# 09_Misc.net
KiCad netlist of a schematic drawn in Altium Designer
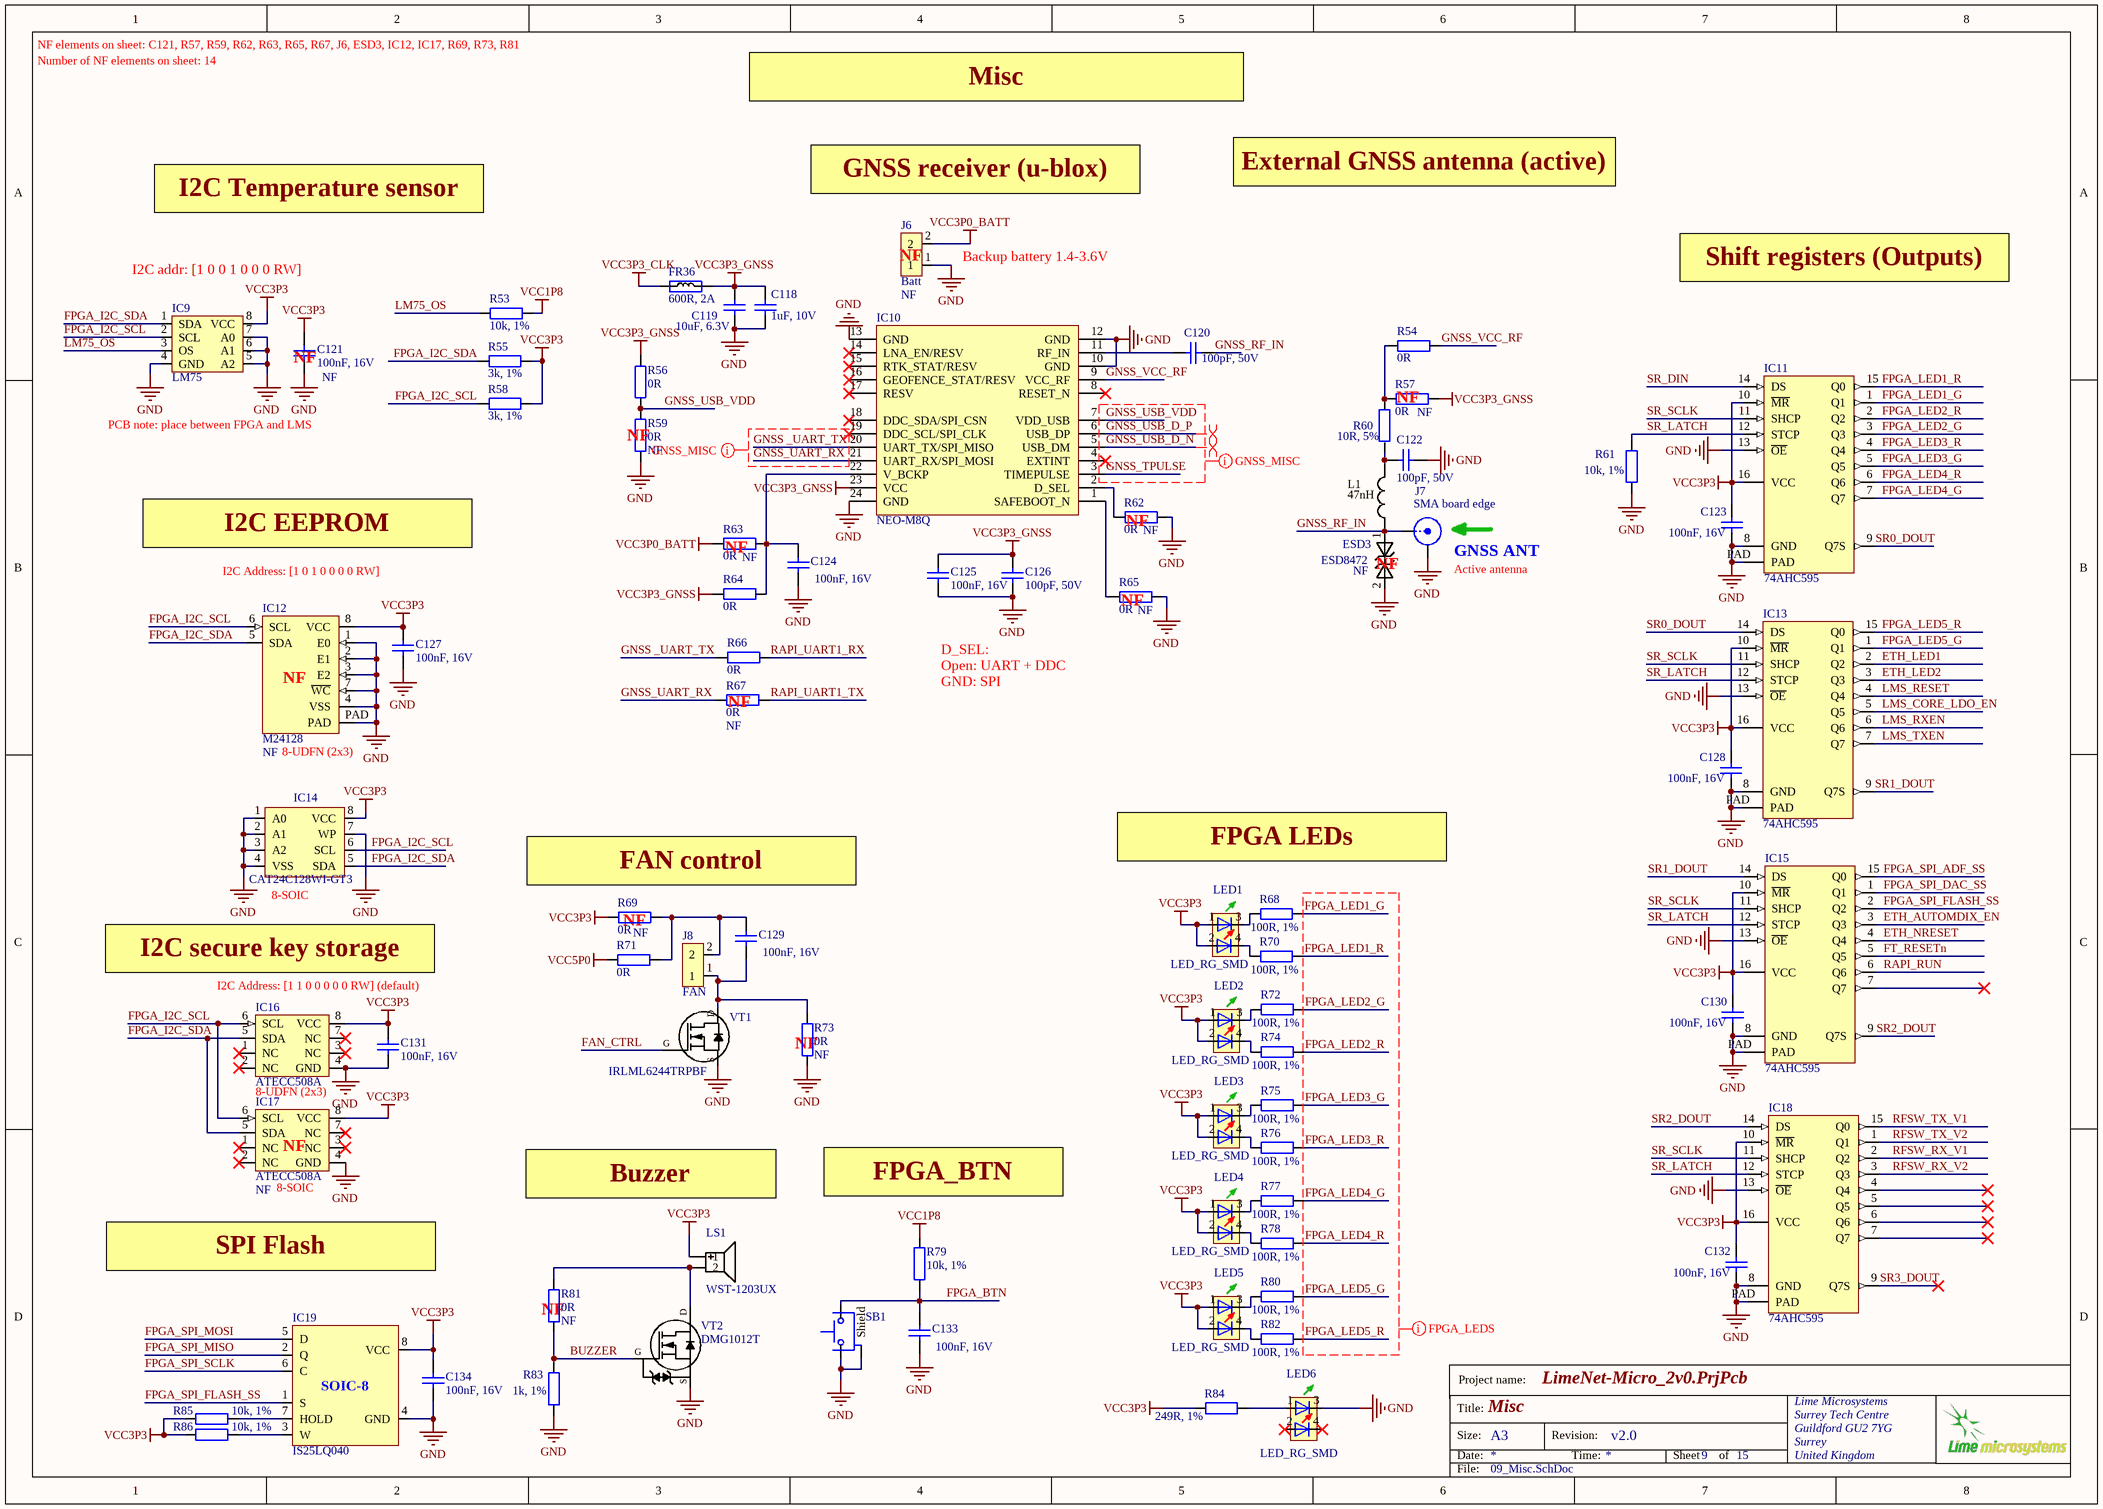
[diagram p0: 09_Misc.SchDoc]

(export (version "E")
  (design (tool "Eeschema 10.0.6"))
  (components
    (comp (ref "C118")
      (value "1uF, 10V")
      (footprint "CAP0402")
      (description "CAP CER 1UF 10V X5R 0402")
      (fields
        (field (name "MANUFACTURER") "Yageo")
        (field (name "MANUFACTURER PART NUMBER") "CC0402MRX5R6BB105")
      )
      (libsource (lib "LimeMicroAltiumLib_schLib") (part "Cap_0402"))
    )
    (comp (ref "C119")
      (value "10uF, 6.3V")
      (footprint "CAP0603")
      (fields (field (name "TOLERANCE") "±20%") (field (name "MANUFACTURER") "Yageo"))
      (libsource (lib "LimeFPGAboard_schLib") (part "Cap_0603"))
    )
    (comp (ref "C120")
      (value "100pF, 50V")
      (footprint "CAP0402")
      (fields (field (name "TOLERANCE") "±5%") (field (name "MANUFACTURER") "Yageo"))
      (libsource (lib "LimeMicroAltiumLib_schLib") (part "Cap_0402"))
    )
    (comp (ref "C121")
      (value "100nF, 16V")
      (footprint "CAP0402")
      (fields
        (field (name "TOLERANCE") "10 %")
        (field (name "MANUFACTURER") "Murata Electronics")
        (field (name "MANUFACTURER PART NUMBER") "GRM155R71C104KA88D")
        (field (name "ASSEMBLY INFO") "NF")
      )
      (libsource (lib "LimeFPGAboard_schLib") (part "Cap_0603"))
    )
    (comp (ref "C122")
      (value "100pF, 50V")
      (footprint "CAP0402")
      (fields (field (name "TOLERANCE") "±5%") (field (name "MANUFACTURER") "Yageo"))
      (libsource (lib "LimeMicroAltiumLib_schLib") (part "Cap_0402"))
    )
    (comp (ref "C123")
      (value "100nF, 16V")
      (footprint "CAP0402")
      (fields
        (field (name "MANUFACTURER") "Murata Electronics")
        (field (name "TOLERANCE") "10 %")
        (field (name "MANUFACTURER PART NUMBER") "GRM155R71C104KA88D")
      )
      (libsource (lib "LimeMicroAltiumLib_schLib") (part "Cap_0402"))
    )
    (comp (ref "C124")
      (value "100nF, 16V")
      (footprint "CAP0402")
      (fields
        (field (name "TOLERANCE") "10 %")
        (field (name "MANUFACTURER") "Murata Electronics")
        (field (name "MANUFACTURER PART NUMBER") "GRM155R71C104KA88D")
      )
      (libsource (lib "LimeFPGAboard_schLib") (part "Cap_0603"))
    )
    (comp (ref "C125")
      (value "100nF, 16V")
      (footprint "CAP0402")
      (fields
        (field (name "MANUFACTURER") "Murata Electronics")
        (field (name "TOLERANCE") "10 %")
        (field (name "MANUFACTURER PART NUMBER") "GRM155R71C104KA88D")
      )
      (libsource (lib "LimeMicroAltiumLib_schLib") (part "Cap_0402"))
    )
    (comp (ref "C126")
      (value "100pF, 50V")
      (footprint "CAP0402")
      (fields (field (name "TOLERANCE") "±5%") (field (name "MANUFACTURER") "Yageo"))
      (libsource (lib "LimeMicroAltiumLib_schLib") (part "Cap_0402"))
    )
    (comp (ref "C127")
      (value "100nF, 16V")
      (footprint "CAP0402")
      (fields
        (field (name "TOLERANCE") "10 %")
        (field (name "MANUFACTURER") "Murata Electronics")
        (field (name "MANUFACTURER PART NUMBER") "GRM155R71C104KA88D")
      )
      (libsource (lib "LimeFPGAboard_schLib") (part "Cap_0603"))
    )
    (comp (ref "C128")
      (value "100nF, 16V")
      (footprint "CAP0402")
      (fields
        (field (name "MANUFACTURER") "Murata Electronics")
        (field (name "TOLERANCE") "10 %")
        (field (name "MANUFACTURER PART NUMBER") "GRM155R71C104KA88D")
      )
      (libsource (lib "LimeMicroAltiumLib_schLib") (part "Cap_0402"))
    )
    (comp (ref "C129")
      (value "100nF, 16V")
      (footprint "CAP0402")
      (fields
        (field (name "TOLERANCE") "10 %")
        (field (name "MANUFACTURER") "Murata Electronics")
        (field (name "MANUFACTURER PART NUMBER") "GRM155R71C104KA88D")
      )
      (libsource (lib "LimeFPGAboard_schLib") (part "Cap_0603"))
    )
    (comp (ref "C130")
      (value "100nF, 16V")
      (footprint "CAP0402")
      (fields
        (field (name "MANUFACTURER") "Murata Electronics")
        (field (name "TOLERANCE") "10 %")
        (field (name "MANUFACTURER PART NUMBER") "GRM155R71C104KA88D")
      )
      (libsource (lib "LimeMicroAltiumLib_schLib") (part "Cap_0402"))
    )
    (comp (ref "C131")
      (value "100nF, 16V")
      (footprint "CAP0402")
      (fields
        (field (name "TOLERANCE") "10 %")
        (field (name "MANUFACTURER") "Murata Electronics")
        (field (name "MANUFACTURER PART NUMBER") "GRM155R71C104KA88D")
      )
      (libsource (lib "LimeFPGAboard_schLib") (part "Cap_0603"))
    )
    (comp (ref "C132")
      (value "100nF, 16V")
      (footprint "CAP0402")
      (fields
        (field (name "MANUFACTURER") "Murata Electronics")
        (field (name "TOLERANCE") "10 %")
        (field (name "MANUFACTURER PART NUMBER") "GRM155R71C104KA88D")
      )
      (libsource (lib "LimeMicroAltiumLib_schLib") (part "Cap_0402"))
    )
    (comp (ref "C133")
      (value "100nF, 16V")
      (footprint "CAP0402")
      (fields
        (field (name "TOLERANCE") "10 %")
        (field (name "MANUFACTURER") "Murata Electronics")
        (field (name "MANUFACTURER PART NUMBER") "GRM155R71C104KA88D")
      )
      (libsource (lib "LimeFPGAboard_schLib") (part "Cap_0603"))
    )
    (comp (ref "C134")
      (value "100nF, 16V")
      (footprint "CAP0402")
      (fields
        (field (name "TOLERANCE") "10 %")
        (field (name "MANUFACTURER") "Murata Electronics")
        (field (name "MANUFACTURER PART NUMBER") "GRM155R71C104KA88D")
      )
      (libsource (lib "LimeFPGAboard_schLib") (part "Cap_0603"))
    )
    (comp (ref "ESD3")
      (value "ESD8472")
      (footprint "ESD8472_X3DFN2")
      (fields
        (field (name "MANUFACTURER") "ON Semiconductor")
        (field (name "MANUFACTURER PART NUMBER") "ESD8472MUT5G")
        (field (name "ASSEMBLY INFO") "NF")
      )
      (libsource (lib "LimeMicroAltiumLib_schLib") (part "ESD8472"))
    )
    (comp (ref "FR36")
      (value "600R, 2A")
      (footprint "RES0805")
      (fields (field (name "MANUFACTURER") "TDK Corporation"))
      (libsource (lib "LimeFPGAboard_schLib") (part "Ferrite"))
    )
    (comp (ref "IC9")
      (value "LM75")
      (footprint "HWSON8_LM75")
      (fields
        (field (name "MANUFACTURER") "NXP Semiconductors")
        (field (name "MANUFACTURER PART NUMBER") "LM75BTP,147")
      )
      (libsource (lib "LimeMicroAltiumLib_schLib") (part "LM75"))
    )
    (comp (ref "IC10")
      (value "NEO-M8Q")
      (footprint "NEO-7M/8M")
      (description "GNSS engine for GPS/QZSS, GLONASS")
      (fields (field (name "MANUFACTURER") "U-blox"))
      (libsource (lib "LimeMicroAltiumLib_schLib") (part "NEO-M8P_M8M"))
    )
    (comp (ref "IC11")
      (value "74AHC595")
      (footprint "74HC595BQ,115")
      (fields (field (name "MANUFACTURER") "Nexperia USA Inc."))
      (libsource (lib "LimeMicroAltiumLib_schLib") (part "74HC595BQ,115"))
    )
    (comp (ref "IC12")
      (value "M24128")
      (footprint "M24128-DFMC6TG")
      (fields (field (name "MANUFACTURER") "STMicroelectronics") (field (name "ASSEMBLY INFO") "NF"))
      (libsource (lib "LimeMicroAltiumLib_schLib") (part "M24128-DFMC6TG"))
    )
    (comp (ref "IC13")
      (value "74AHC595")
      (footprint "74HC595BQ,115")
      (fields (field (name "MANUFACTURER") "Nexperia USA Inc."))
      (libsource (lib "LimeMicroAltiumLib_schLib") (part "74HC595BQ,115"))
    )
    (comp (ref "IC14")
      (value "CAT24C128WI-GT3")
      (footprint "SOIC127P600-8DL_v2")
      (fields (field (name "MANUFACTURER") "ON Semiconductor") (field (name "BASE PART NUMBER") "CAT24C128"))
      (libsource (lib "LimeMicroAltiumLib_schLib") (part "24FC64F"))
    )
    (comp (ref "IC15")
      (value "74AHC595")
      (footprint "74HC595BQ,115")
      (fields (field (name "MANUFACTURER") "Nexperia USA Inc."))
      (libsource (lib "LimeMicroAltiumLib_schLib") (part "74HC595BQ,115"))
    )
    (comp (ref "IC16")
      (value "ATECC508A")
      (footprint "ATECC508A_UDFN8")
      (fields (field (name "MANUFACTURER") "Microchip"))
      (libsource (lib "LimeMicroAltiumLib_schLib_r01") (part "ATECC508A_authentication_IC"))
    )
    (comp (ref "IC17")
      (value "ATECC508A")
      (footprint "SOIC127P600-8DL_v2")
      (fields
        (field (name "ASSEMBLY INFO") "NF")
        (field (name "MANUFACTURER") "Microchip Technology")
        (field (name "BASE PART NUMBER") "ATECC508")
      )
      (libsource (lib "LimeMicroAltiumLib_schLib_r01") (part "ATECC508A_authentication_IC"))
    )
    (comp (ref "IC18")
      (value "74AHC595")
      (footprint "74HC595BQ,115")
      (fields (field (name "MANUFACTURER") "Nexperia USA Inc."))
      (libsource (lib "LimeMicroAltiumLib_schLib") (part "74HC595BQ,115"))
    )
    (comp (ref "IC19")
      (value "IS25LQ040")
      (footprint "M25P40-VMN6TPB_SO8N")
      (fields
        (field (name "MANUFACTURER PART NUMBER") "IS25LQ040B-JNLE")
        (field (name "MANUFACTURER") "ISSI, Integrated Silicon Solution Inc")
      )
      (libsource (lib "LimeFPGAboard_schLib") (part "M25P40"))
    )
    (comp (ref "J6")
      (value "Batt")
      (footprint "HDR_1x2")
      (fields (field (name "ASSEMBLY INFO") "NF") (field (name "MANUFACTURER") "3M"))
      (libsource (lib "LimeFPGAboard_schLib") (part "Jumper"))
    )
    (comp (ref "J7")
      (value "SMA board edge")
      (footprint "SMA_connector_board_edge_SM")
      (description "CONN SMA JACK STR 50OHM EDGE MNT")
      (fields (field (name "MANUFACTURER") "RF Solutions"))
      (libsource (lib "LimeMicroAltiumLib_schLib") (part "RF_IF_connector"))
    )
    (comp (ref "J8")
      (value "FAN")
      (footprint "HDR_1x2")
      (fields (field (name "MANUFACTURER") "3M"))
      (libsource (lib "LimeFPGAboard_schLib") (part "Jumper"))
    )
    (comp (ref "L1")
      (value "47nH")
      (footprint "RES0402")
      (fields
        (field (name "MANUFACTURER") "COILCRAFT")
        (field (name "MANUFACTURER PART NUMBER") "0402HP-47NXJLU")
      )
      (libsource (lib "LimeMicroAltiumLib_schLib") (part "Inductor_0603"))
    )
    (comp (ref "LED1")
      (value "LED_RG_SMD")
      (footprint "LED-2x0603")
      (fields (field (name "MANUFACTURER") "Avago Technologies US Inc."))
      (libsource (lib "LimeMicroAltiumLib_schLib") (part "LED_green_red_SMD"))
    )
    (comp (ref "LED2")
      (value "LED_RG_SMD")
      (footprint "LED-2x0603")
      (fields (field (name "MANUFACTURER") "Avago Technologies US Inc."))
      (libsource (lib "LimeMicroAltiumLib_schLib") (part "LED_green_red_SMD"))
    )
    (comp (ref "LED3")
      (value "LED_RG_SMD")
      (footprint "LED-2x0603")
      (fields (field (name "MANUFACTURER") "Avago Technologies US Inc."))
      (libsource (lib "LimeMicroAltiumLib_schLib") (part "LED_green_red_SMD"))
    )
    (comp (ref "LED4")
      (value "LED_RG_SMD")
      (footprint "LED-2x0603")
      (fields (field (name "MANUFACTURER") "Avago Technologies US Inc."))
      (libsource (lib "LimeMicroAltiumLib_schLib") (part "LED_green_red_SMD"))
    )
    (comp (ref "LED5")
      (value "LED_RG_SMD")
      (footprint "LED-2x0603")
      (fields (field (name "MANUFACTURER") "Avago Technologies US Inc."))
      (libsource (lib "LimeMicroAltiumLib_schLib") (part "LED_green_red_SMD"))
    )
    (comp (ref "LED6")
      (value "LED_RG_SMD")
      (footprint "LED-2x0603")
      (fields (field (name "MANUFACTURER") "Avago Technologies US Inc."))
      (libsource (lib "LimeMicroAltiumLib_schLib") (part "LED_green_red_SMD"))
    )
    (comp (ref "LS1")
      (value "WST-1203UX")
      (footprint "BUZZER_WST-1203UX")
      (fields (field (name "MANUFACTURER") "Soberton Inc."))
      (libsource (lib "LimeMicroAltiumLib_schLib_r01") (part "BUZZER_WST-1203UX"))
    )
    (comp (ref "R53")
      (value "10k, 1%")
      (footprint "RES0402")
      (fields (field (name "MANUFACTURER") "Yageo") (field (name "TOLERANCE") "±1%"))
      (libsource (lib "LimeMicroAltiumLib_schLib") (part "Res_0402"))
    )
    (comp (ref "R54")
      (value "0R")
      (footprint "RES0402")
      (fields (field (name "MANUFACTURER") "Yageo") (field (name "TOLERANCE") "Jumper"))
      (libsource (lib "LimeMicroAltiumLib_schLib") (part "Res_0402"))
    )
    (comp (ref "R55")
      (value "3k, 1%")
      (footprint "RES0402")
      (fields (field (name "TOLERANCE") "±1%") (field (name "MANUFACTURER") "Vishay Dale"))
      (libsource (lib "LimeMicroAltiumLib_schLib") (part "Res_0402"))
    )
    (comp (ref "R56")
      (value "0R")
      (footprint "RES0402")
      (fields (field (name "MANUFACTURER") "Yageo") (field (name "TOLERANCE") "Jumper"))
      (libsource (lib "LimeMicroAltiumLib_schLib") (part "Res_0402"))
    )
    (comp (ref "R57")
      (value "0R")
      (footprint "RES0402")
      (fields
        (field (name "ASSEMBLY INFO") "NF")
        (field (name "MANUFACTURER") "Yageo")
        (field (name "TOLERANCE") "Jumper")
      )
      (libsource (lib "LimeMicroAltiumLib_schLib") (part "Res_0402"))
    )
    (comp (ref "R58")
      (value "3k, 1%")
      (footprint "RES0402")
      (fields (field (name "TOLERANCE") "±1%") (field (name "MANUFACTURER") "Vishay Dale"))
      (libsource (lib "LimeMicroAltiumLib_schLib") (part "Res_0402"))
    )
    (comp (ref "R59")
      (value "0R")
      (footprint "RES0402")
      (fields
        (field (name "ASSEMBLY INFO") "NF")
        (field (name "MANUFACTURER") "Yageo")
        (field (name "TOLERANCE") "Jumper")
      )
      (libsource (lib "LimeMicroAltiumLib_schLib") (part "Res_0402"))
    )
    (comp (ref "R60")
      (value "10R, 5%")
      (footprint "RES0402")
      (fields (field (name "TOLERANCE") "±5%") (field (name "MANUFACTURER") "Yageo"))
      (libsource (lib "LimeMicroAltiumLib_schLib") (part "Res_0402"))
    )
    (comp (ref "R61")
      (value "10k, 1%")
      (footprint "RES0402")
      (fields (field (name "MANUFACTURER") "Yageo") (field (name "TOLERANCE") "±1%"))
      (libsource (lib "LimeMicroAltiumLib_schLib") (part "Res_0402"))
    )
    (comp (ref "R62")
      (value "0R")
      (footprint "RES0402")
      (fields
        (field (name "ASSEMBLY INFO") "NF")
        (field (name "MANUFACTURER") "Yageo")
        (field (name "TOLERANCE") "Jumper")
      )
      (libsource (lib "LimeMicroAltiumLib_schLib") (part "Res_0402"))
    )
    (comp (ref "R63")
      (value "0R")
      (footprint "RES0402")
      (fields
        (field (name "ASSEMBLY INFO") "NF")
        (field (name "MANUFACTURER") "Yageo")
        (field (name "TOLERANCE") "Jumper")
      )
      (libsource (lib "LimeMicroAltiumLib_schLib") (part "Res_0402"))
    )
    (comp (ref "R64")
      (value "0R")
      (footprint "RES0402")
      (fields (field (name "MANUFACTURER") "Yageo") (field (name "TOLERANCE") "Jumper"))
      (libsource (lib "LimeMicroAltiumLib_schLib") (part "Res_0402"))
    )
    (comp (ref "R65")
      (value "0R")
      (footprint "RES0402")
      (fields
        (field (name "ASSEMBLY INFO") "NF")
        (field (name "MANUFACTURER") "Yageo")
        (field (name "TOLERANCE") "Jumper")
      )
      (libsource (lib "LimeMicroAltiumLib_schLib") (part "Res_0402"))
    )
    (comp (ref "R66")
      (value "0R")
      (footprint "RES0402")
      (fields (field (name "MANUFACTURER") "Yageo") (field (name "TOLERANCE") "Jumper"))
      (libsource (lib "LimeMicroAltiumLib_schLib") (part "Res_0402"))
    )
    (comp (ref "R67")
      (value "0R")
      (footprint "RES0402")
      (fields
        (field (name "ASSEMBLY INFO") "NF")
        (field (name "MANUFACTURER") "Yageo")
        (field (name "TOLERANCE") "Jumper")
      )
      (libsource (lib "LimeMicroAltiumLib_schLib") (part "Res_0402"))
    )
    (comp (ref "R68")
      (value "100R, 1%")
      (footprint "RES0402")
      (fields (field (name "TOLERANCE") "±1%") (field (name "MANUFACTURER") "Stackpole Electronics Inc."))
      (libsource (lib "LimeMicroAltiumLib_schLib") (part "Res_0402"))
    )
    (comp (ref "R69")
      (value "0R")
      (footprint "RES0402")
      (fields
        (field (name "ASSEMBLY INFO") "NF")
        (field (name "MANUFACTURER") "Yageo")
        (field (name "TOLERANCE") "Jumper")
      )
      (libsource (lib "LimeMicroAltiumLib_schLib") (part "Res_0402"))
    )
    (comp (ref "R70")
      (value "100R, 1%")
      (footprint "RES0402")
      (fields (field (name "TOLERANCE") "±1%") (field (name "MANUFACTURER") "Stackpole Electronics Inc."))
      (libsource (lib "LimeMicroAltiumLib_schLib") (part "Res_0402"))
    )
    (comp (ref "R71")
      (value "0R")
      (footprint "RES0402")
      (fields (field (name "MANUFACTURER") "Yageo") (field (name "TOLERANCE") "Jumper"))
      (libsource (lib "LimeMicroAltiumLib_schLib") (part "Res_0402"))
    )
    (comp (ref "R72")
      (value "100R, 1%")
      (footprint "RES0402")
      (fields (field (name "TOLERANCE") "±1%") (field (name "MANUFACTURER") "Stackpole Electronics Inc."))
      (libsource (lib "LimeMicroAltiumLib_schLib") (part "Res_0402"))
    )
    (comp (ref "R73")
      (value "0R")
      (footprint "RES0402")
      (fields
        (field (name "ASSEMBLY INFO") "NF")
        (field (name "MANUFACTURER") "Yageo")
        (field (name "TOLERANCE") "Jumper")
      )
      (libsource (lib "LimeMicroAltiumLib_schLib") (part "Res_0402"))
    )
    (comp (ref "R74")
      (value "100R, 1%")
      (footprint "RES0402")
      (fields (field (name "TOLERANCE") "±1%") (field (name "MANUFACTURER") "Stackpole Electronics Inc."))
      (libsource (lib "LimeMicroAltiumLib_schLib") (part "Res_0402"))
    )
    (comp (ref "R75")
      (value "100R, 1%")
      (footprint "RES0402")
      (fields (field (name "TOLERANCE") "±1%") (field (name "MANUFACTURER") "Stackpole Electronics Inc."))
      (libsource (lib "LimeMicroAltiumLib_schLib") (part "Res_0402"))
    )
    (comp (ref "R76")
      (value "100R, 1%")
      (footprint "RES0402")
      (fields (field (name "TOLERANCE") "±1%") (field (name "MANUFACTURER") "Stackpole Electronics Inc."))
      (libsource (lib "LimeMicroAltiumLib_schLib") (part "Res_0402"))
    )
    (comp (ref "R77")
      (value "100R, 1%")
      (footprint "RES0402")
      (fields (field (name "TOLERANCE") "±1%") (field (name "MANUFACTURER") "Stackpole Electronics Inc."))
      (libsource (lib "LimeMicroAltiumLib_schLib") (part "Res_0402"))
    )
    (comp (ref "R78")
      (value "100R, 1%")
      (footprint "RES0402")
      (fields (field (name "TOLERANCE") "±1%") (field (name "MANUFACTURER") "Stackpole Electronics Inc."))
      (libsource (lib "LimeMicroAltiumLib_schLib") (part "Res_0402"))
    )
    (comp (ref "R79")
      (value "10k, 1%")
      (footprint "RES0402")
      (fields (field (name "MANUFACTURER") "Yageo") (field (name "TOLERANCE") "±1%"))
      (libsource (lib "LimeMicroAltiumLib_schLib") (part "Res_0402"))
    )
    (comp (ref "R80")
      (value "100R, 1%")
      (footprint "RES0402")
      (fields (field (name "TOLERANCE") "±1%") (field (name "MANUFACTURER") "Stackpole Electronics Inc."))
      (libsource (lib "LimeMicroAltiumLib_schLib") (part "Res_0402"))
    )
    (comp (ref "R81")
      (value "0R")
      (footprint "RES0402")
      (fields
        (field (name "ASSEMBLY INFO") "NF")
        (field (name "MANUFACTURER") "Yageo")
        (field (name "TOLERANCE") "Jumper")
      )
      (libsource (lib "LimeMicroAltiumLib_schLib") (part "Res_0402"))
    )
    (comp (ref "R82")
      (value "100R, 1%")
      (footprint "RES0402")
      (fields (field (name "TOLERANCE") "±1%") (field (name "MANUFACTURER") "Stackpole Electronics Inc."))
      (libsource (lib "LimeMicroAltiumLib_schLib") (part "Res_0402"))
    )
    (comp (ref "R83")
      (value "1k, 1%")
      (footprint "RES0402")
      (fields (field (name "MANUFACTURER") "Stackpole Electronics Inc") (field (name "TOLERANCE") "±1%"))
      (libsource (lib "LimeMicroAltiumLib_schLib") (part "Res_0402"))
    )
    (comp (ref "R84")
      (value "249R, 1%")
      (footprint "RES0402")
      (fields (field (name "MANUFACTURER") "Stackpole Electronics Inc") (field (name "TOLERANCE") "±1%"))
      (libsource (lib "LimeMicroAltiumLib_schLib") (part "Res_0402"))
    )
    (comp (ref "R85")
      (value "10k, 1%")
      (footprint "RES0402")
      (fields (field (name "MANUFACTURER") "Yageo") (field (name "TOLERANCE") "±1%"))
      (libsource (lib "LimeMicroAltiumLib_schLib") (part "Res_0402"))
    )
    (comp (ref "R86")
      (value "10k, 1%")
      (footprint "RES0402")
      (fields (field (name "MANUFACTURER") "Yageo") (field (name "TOLERANCE") "±1%"))
      (libsource (lib "LimeMicroAltiumLib_schLib") (part "Res_0402"))
    )
    (comp (ref "SB1")
      (value "Switch tactile right edge")
      (footprint "SW_TACTILE_RIGHT_EDGE")
      (fields (field (name "MANUFACTURER") "TE Connectivity ALCOSWITCH Switches"))
      (libsource (lib "LimeMicroAltiumLib_schLib_r01") (part "Button_right_edge"))
    )
    (comp (ref "VT1")
      (value "IRLML6244TRPBF")
      (footprint "SOT23-3")
      (description "NDS331N")
      (fields (field (name "MANUFACTURER") "Infineon Technologies"))
      (libsource (lib "LimeFPGAboard_schLib") (part "NDS331N"))
    )
    (comp (ref "VT2")
      (value "DMG1012T")
      (footprint "SOT523")
      (fields
        (field (name "MANUFACTURER") "Diodes Incorporated")
        (field (name "MANUFACTURER PART NUMBER") "DMG1012TQ-7")
      )
      (libsource (lib "LimeMicroAltiumLib_schLib_r01") (part "DMG1012T"))
    )
  )
  (nets
    (net (code "1") (name "/BUZZER") (class "Default")
      (node (ref "R81") (pin "1") (pinfunction "1_1") (pintype "passive"))
      (node (ref "R83") (pin "1") (pinfunction "1_1") (pintype "passive"))
      (node (ref "VT2") (pin "G") (pinfunction "G_G") (pintype "passive"))
    )
    (net (code "2") (name "/ETH_AUTOMDIX_EN") (class "Default")
      (node (ref "IC15") (pin "3") (pinfunction "Q3_3") (pintype "output"))
    )
    (net (code "3") (name "/ETH_LED1") (class "Default")
      (node (ref "IC13") (pin "2") (pinfunction "Q2_2") (pintype "output"))
    )
    (net (code "4") (name "/ETH_LED2") (class "Default")
      (node (ref "IC13") (pin "3") (pinfunction "Q3_3") (pintype "output"))
    )
    (net (code "5") (name "/ETH_NRESET") (class "Default")
      (node (ref "IC15") (pin "4") (pinfunction "Q4_4") (pintype "output"))
    )
    (net (code "6") (name "/FAN_CTRL") (class "Default")
      (node (ref "VT1") (pin "G") (pinfunction "G_G") (pintype "passive"))
    )
    (net (code "7") (name "/FPGA_BTN") (class "Default")
      (node (ref "C133") (pin "1") (pinfunction "1_1") (pintype "passive"))
      (node (ref "R79") (pin "2") (pinfunction "2_2") (pintype "passive"))
      (node (ref "SB1") (pin "1") (pinfunction "1_1") (pintype "passive"))
    )
    (net (code "8") (name "/FPGA_I2C_SCL") (class "Default")
      (node (ref "IC12") (pin "6") (pinfunction "SCL_6") (pintype "input"))
      (node (ref "IC14") (pin "6") (pinfunction "SCL_6") (pintype "passive"))
      (node (ref "IC16") (pin "6") (pinfunction "SCL_6") (pintype "input"))
      (node (ref "IC17") (pin "6") (pinfunction "SCL_6") (pintype "input"))
      (node (ref "IC9") (pin "2") (pinfunction "SCL_2") (pintype "passive"))
      (node (ref "R58") (pin "2") (pinfunction "2_2") (pintype "passive"))
    )
    (net (code "9") (name "/FPGA_I2C_SDA") (class "Default")
      (node (ref "IC12") (pin "5") (pinfunction "SDA_5") (pintype "bidirectional"))
      (node (ref "IC14") (pin "5") (pinfunction "SDA_5") (pintype "passive"))
      (node (ref "IC16") (pin "5") (pinfunction "SDA_5") (pintype "bidirectional"))
      (node (ref "IC17") (pin "5") (pinfunction "SDA_5") (pintype "bidirectional"))
      (node (ref "IC9") (pin "1") (pinfunction "SDA_1") (pintype "passive"))
      (node (ref "R55") (pin "2") (pinfunction "2_2") (pintype "passive"))
    )
    (net (code "10") (name "/FPGA_LED1_G") (class "Default")
      (node (ref "IC11") (pin "1") (pinfunction "Q1_1") (pintype "output"))
      (node (ref "R68") (pin "2") (pinfunction "2_2") (pintype "passive"))
    )
    (net (code "11") (name "/FPGA_LED1_R") (class "Default")
      (node (ref "IC11") (pin "15") (pinfunction "Q0_15") (pintype "output"))
      (node (ref "R70") (pin "2") (pinfunction "2_2") (pintype "passive"))
    )
    (net (code "12") (name "/FPGA_LED2_G") (class "Default")
      (node (ref "IC11") (pin "3") (pinfunction "Q3_3") (pintype "output"))
      (node (ref "R72") (pin "2") (pinfunction "2_2") (pintype "passive"))
    )
    (net (code "13") (name "/FPGA_LED2_R") (class "Default")
      (node (ref "IC11") (pin "2") (pinfunction "Q2_2") (pintype "output"))
      (node (ref "R74") (pin "2") (pinfunction "2_2") (pintype "passive"))
    )
    (net (code "14") (name "/FPGA_LED3_G") (class "Default")
      (node (ref "IC11") (pin "5") (pinfunction "Q5_5") (pintype "output"))
      (node (ref "R75") (pin "2") (pinfunction "2_2") (pintype "passive"))
    )
    (net (code "15") (name "/FPGA_LED3_R") (class "Default")
      (node (ref "IC11") (pin "4") (pinfunction "Q4_4") (pintype "output"))
      (node (ref "R76") (pin "2") (pinfunction "2_2") (pintype "passive"))
    )
    (net (code "16") (name "/FPGA_LED4_G") (class "Default")
      (node (ref "IC11") (pin "7") (pinfunction "Q7_7") (pintype "output"))
      (node (ref "R77") (pin "2") (pinfunction "2_2") (pintype "passive"))
    )
    (net (code "17") (name "/FPGA_LED4_R") (class "Default")
      (node (ref "IC11") (pin "6") (pinfunction "Q6_6") (pintype "output"))
      (node (ref "R78") (pin "2") (pinfunction "2_2") (pintype "passive"))
    )
    (net (code "18") (name "/FPGA_LED5_G") (class "Default")
      (node (ref "IC13") (pin "1") (pinfunction "Q1_1") (pintype "output"))
      (node (ref "R80") (pin "2") (pinfunction "2_2") (pintype "passive"))
    )
    (net (code "19") (name "/FPGA_LED5_R") (class "Default")
      (node (ref "IC13") (pin "15") (pinfunction "Q0_15") (pintype "output"))
      (node (ref "R82") (pin "2") (pinfunction "2_2") (pintype "passive"))
    )
    (net (code "20") (name "/FPGA_SPI_ADF_SS") (class "Default")
      (node (ref "IC15") (pin "15") (pinfunction "Q0_15") (pintype "output"))
    )
    (net (code "21") (name "/FPGA_SPI_DAC_SS") (class "Default")
      (node (ref "IC15") (pin "1") (pinfunction "Q1_1") (pintype "output"))
    )
    (net (code "22") (name "/FPGA_SPI_FLASH_SS") (class "Default")
      (node (ref "IC15") (pin "2") (pinfunction "Q2_2") (pintype "output"))
      (node (ref "IC19") (pin "1") (pinfunction "S_1") (pintype "passive"))
    )
    (net (code "23") (name "/FPGA_SPI_MISO") (class "Default")
      (node (ref "IC19") (pin "2") (pinfunction "Q_2") (pintype "passive"))
    )
    (net (code "24") (name "/FPGA_SPI_MOSI") (class "Default")
      (node (ref "IC19") (pin "5") (pinfunction "D_5") (pintype "passive"))
    )
    (net (code "25") (name "/FPGA_SPI_SCLK") (class "Default")
      (node (ref "IC19") (pin "6") (pinfunction "C_6") (pintype "passive"))
    )
    (net (code "26") (name "/FT_RESETn") (class "Default")
      (node (ref "IC15") (pin "5") (pinfunction "Q5_5") (pintype "output"))
    )
    (net (code "27") (name "/GNSS _UART_TX") (class "Default")
      (node (ref "IC10") (pin "20") (pinfunction "UART_TX/SPI_MISO_20") (pintype "passive"))
      (node (ref "R66") (pin "2") (pinfunction "2_2") (pintype "passive"))
    )
    (net (code "28") (name "/GNSS_RF_IN") (class "Default")
      (node (ref "C120") (pin "1") (pinfunction "1_1") (pintype "passive"))
      (node (ref "ESD3") (pin "1") (pinfunction "1_1") (pintype "passive"))
      (node (ref "J7") (pin "1") (pinfunction "X_1") (pintype "passive"))
      (node (ref "L1") (pin "1") (pinfunction "1_1") (pintype "passive"))
    )
    (net (code "29") (name "/GNSS_TPULSE") (class "Default")
      (node (ref "IC10") (pin "3") (pinfunction "TIMEPULSE_3") (pintype "passive"))
    )
    (net (code "30") (name "/GNSS_UART_RX") (class "Default")
      (node (ref "IC10") (pin "21") (pinfunction "UART_RX/SPI_MOSI_21") (pintype "passive"))
      (node (ref "R67") (pin "1") (pinfunction "1_1") (pintype "passive"))
    )
    (net (code "31") (name "/GNSS_USB_D_N") (class "Default")
      (node (ref "IC10") (pin "5") (pinfunction "USB_DM_5") (pintype "passive"))
    )
    (net (code "32") (name "/GNSS_USB_D_P") (class "Default")
      (node (ref "IC10") (pin "6") (pinfunction "USB_DP_6") (pintype "passive"))
    )
    (net (code "33") (name "/GNSS_USB_VDD") (class "Default")
      (node (ref "IC10") (pin "7") (pinfunction "VDD_USB_7") (pintype "passive"))
      (node (ref "R56") (pin "1") (pinfunction "1_1") (pintype "passive"))
      (node (ref "R59") (pin "1") (pinfunction "1_1") (pintype "passive"))
    )
    (net (code "34") (name "/GNSS_VCC_RF") (class "Default")
      (node (ref "IC10") (pin "9") (pinfunction "VCC_RF_9") (pintype "passive"))
      (node (ref "R54") (pin "2") (pinfunction "2_2") (pintype "passive"))
    )
    (net (code "35") (name "/LM75_OS") (class "Default")
      (node (ref "IC9") (pin "3") (pinfunction "OS_3") (pintype "passive"))
      (node (ref "R53") (pin "1") (pinfunction "1_1") (pintype "passive"))
    )
    (net (code "36") (name "/LMS_CORE_LDO_EN") (class "Default")
      (node (ref "IC13") (pin "5") (pinfunction "Q5_5") (pintype "output"))
    )
    (net (code "37") (name "/LMS_RESET") (class "Default")
      (node (ref "IC13") (pin "4") (pinfunction "Q4_4") (pintype "output"))
    )
    (net (code "38") (name "/LMS_RXEN") (class "Default")
      (node (ref "IC13") (pin "6") (pinfunction "Q6_6") (pintype "output"))
    )
    (net (code "39") (name "/LMS_TXEN") (class "Default")
      (node (ref "IC13") (pin "7") (pinfunction "Q7_7") (pintype "output"))
    )
    (net (code "40") (name "/RAPI_RUN") (class "Default")
      (node (ref "IC15") (pin "6") (pinfunction "Q6_6") (pintype "output"))
    )
    (net (code "41") (name "/RAPI_UART1_RX") (class "Default")
      (node (ref "R66") (pin "1") (pinfunction "1_1") (pintype "passive"))
    )
    (net (code "42") (name "/RAPI_UART1_TX") (class "Default")
      (node (ref "R67") (pin "2") (pinfunction "2_2") (pintype "passive"))
    )
    (net (code "43") (name "/RFSW_RX_V1") (class "Default")
      (node (ref "IC18") (pin "2") (pinfunction "Q2_2") (pintype "output"))
    )
    (net (code "44") (name "/RFSW_RX_V2") (class "Default")
      (node (ref "IC18") (pin "3") (pinfunction "Q3_3") (pintype "output"))
    )
    (net (code "45") (name "/RFSW_TX_V1") (class "Default")
      (node (ref "IC18") (pin "15") (pinfunction "Q0_15") (pintype "output"))
    )
    (net (code "46") (name "/RFSW_TX_V2") (class "Default")
      (node (ref "IC18") (pin "1") (pinfunction "Q1_1") (pintype "output"))
    )
    (net (code "47") (name "/SR0_DOUT") (class "Default")
      (node (ref "IC11") (pin "9") (pinfunction "Q7S_9") (pintype "output"))
      (node (ref "IC13") (pin "14") (pinfunction "DS_14") (pintype "input"))
    )
    (net (code "48") (name "/SR1_DOUT") (class "Default")
      (node (ref "IC13") (pin "9") (pinfunction "Q7S_9") (pintype "output"))
      (node (ref "IC15") (pin "14") (pinfunction "DS_14") (pintype "input"))
    )
    (net (code "49") (name "/SR2_DOUT") (class "Default")
      (node (ref "IC15") (pin "9") (pinfunction "Q7S_9") (pintype "output"))
      (node (ref "IC18") (pin "14") (pinfunction "DS_14") (pintype "input"))
    )
    (net (code "50") (name "/SR3_DOUT") (class "Default")
      (node (ref "IC18") (pin "9") (pinfunction "Q7S_9") (pintype "output+no_connect"))
    )
    (net (code "51") (name "/SR_DIN") (class "Default")
      (node (ref "IC11") (pin "14") (pinfunction "DS_14") (pintype "input"))
    )
    (net (code "52") (name "/SR_LATCH") (class "Default")
      (node (ref "IC11") (pin "12") (pinfunction "STCP_12") (pintype "input"))
      (node (ref "IC13") (pin "12") (pinfunction "STCP_12") (pintype "input"))
      (node (ref "IC15") (pin "12") (pinfunction "STCP_12") (pintype "input"))
      (node (ref "IC18") (pin "12") (pinfunction "STCP_12") (pintype "input"))
      (node (ref "R61") (pin "1") (pinfunction "1_1") (pintype "passive"))
    )
    (net (code "53") (name "/SR_SCLK") (class "Default")
      (node (ref "IC11") (pin "11") (pinfunction "SHCP_11") (pintype "input"))
      (node (ref "IC13") (pin "11") (pinfunction "SHCP_11") (pintype "input"))
      (node (ref "IC15") (pin "11") (pinfunction "SHCP_11") (pintype "input"))
      (node (ref "IC18") (pin "11") (pinfunction "SHCP_11") (pintype "input"))
    )
    (net (code "54") (name "GND") (class "Default")
      (node (ref "C118") (pin "1") (pinfunction "1_1") (pintype "passive"))
      (node (ref "C119") (pin "1") (pinfunction "1_1") (pintype "passive"))
      (node (ref "C121") (pin "2") (pinfunction "2_2") (pintype "passive"))
      (node (ref "C122") (pin "2") (pinfunction "2_2") (pintype "passive"))
      (node (ref "C123") (pin "1") (pinfunction "1_1") (pintype "passive"))
      (node (ref "C124") (pin "2") (pinfunction "2_2") (pintype "passive"))
      (node (ref "C125") (pin "1") (pinfunction "1_1") (pintype "passive"))
      (node (ref "C126") (pin "2") (pinfunction "2_2") (pintype "passive"))
      (node (ref "C127") (pin "2") (pinfunction "2_2") (pintype "passive"))
      (node (ref "C128") (pin "1") (pinfunction "1_1") (pintype "passive"))
      (node (ref "C130") (pin "1") (pinfunction "1_1") (pintype "passive"))
      (node (ref "C131") (pin "2") (pinfunction "2_2") (pintype "passive"))
      (node (ref "C132") (pin "1") (pinfunction "1_1") (pintype "passive"))
      (node (ref "C133") (pin "2") (pinfunction "2_2") (pintype "passive"))
      (node (ref "C134") (pin "2") (pinfunction "2_2") (pintype "passive"))
      (node (ref "ESD3") (pin "2") (pinfunction "2_2") (pintype "passive"))
      (node (ref "IC10") (pin "10") (pinfunction "GND_10") (pintype "passive"))
      (node (ref "IC10") (pin "12") (pinfunction "GND_12") (pintype "passive"))
      (node (ref "IC10") (pin "13") (pinfunction "GND_13") (pintype "passive"))
      (node (ref "IC10") (pin "24") (pinfunction "GND_24") (pintype "passive"))
      (node (ref "IC11") (pin "13") (pinfunction "~{OE}_13") (pintype "input"))
      (node (ref "IC11") (pin "8") (pinfunction "GND_8") (pintype "passive"))
      (node (ref "IC11") (pin "PAD") (pinfunction "PAD_PAD") (pintype "passive"))
      (node (ref "IC12") (pin "1") (pinfunction "E0_1") (pintype "input"))
      (node (ref "IC12") (pin "2") (pinfunction "E1_2") (pintype "input"))
      (node (ref "IC12") (pin "3") (pinfunction "E2_3") (pintype "input"))
      (node (ref "IC12") (pin "4") (pinfunction "VSS_4") (pintype "power_in"))
      (node (ref "IC12") (pin "7") (pinfunction "~{WC}_7") (pintype "input"))
      (node (ref "IC12") (pin "PAD") (pinfunction "PAD_PAD") (pintype "power_in"))
      (node (ref "IC13") (pin "13") (pinfunction "~{OE}_13") (pintype "input"))
      (node (ref "IC13") (pin "8") (pinfunction "GND_8") (pintype "passive"))
      (node (ref "IC13") (pin "PAD") (pinfunction "PAD_PAD") (pintype "passive"))
      (node (ref "IC14") (pin "1") (pinfunction "A0_1") (pintype "passive"))
      (node (ref "IC14") (pin "2") (pinfunction "A1_2") (pintype "passive"))
      (node (ref "IC14") (pin "3") (pinfunction "A2_3") (pintype "passive"))
      (node (ref "IC14") (pin "4") (pinfunction "VSS_4") (pintype "passive"))
      (node (ref "IC14") (pin "7") (pinfunction "WP_7") (pintype "passive"))
      (node (ref "IC15") (pin "13") (pinfunction "~{OE}_13") (pintype "input"))
      (node (ref "IC15") (pin "8") (pinfunction "GND_8") (pintype "passive"))
      (node (ref "IC15") (pin "PAD") (pinfunction "PAD_PAD") (pintype "passive"))
      (node (ref "IC16") (pin "4") (pinfunction "GND_4") (pintype "passive"))
      (node (ref "IC17") (pin "4") (pinfunction "GND_4") (pintype "passive"))
      (node (ref "IC18") (pin "13") (pinfunction "~{OE}_13") (pintype "input"))
      (node (ref "IC18") (pin "8") (pinfunction "GND_8") (pintype "passive"))
      (node (ref "IC18") (pin "PAD") (pinfunction "PAD_PAD") (pintype "passive"))
      (node (ref "IC19") (pin "4") (pinfunction "GND_4") (pintype "passive"))
      (node (ref "IC9") (pin "4") (pinfunction "GND_4") (pintype "passive"))
      (node (ref "IC9") (pin "5") (pinfunction "A2_5") (pintype "passive"))
      (node (ref "IC9") (pin "6") (pinfunction "A1_6") (pintype "passive"))
      (node (ref "IC9") (pin "7") (pinfunction "A0_7") (pintype "passive"))
      (node (ref "J6") (pin "1") (pinfunction "1_1") (pintype "passive"))
      (node (ref "J7") (pin "2") (pinfunction "Y_2") (pintype "passive"))
      (node (ref "LED6") (pin "3") (pinfunction "3_3") (pintype "power_in"))
      (node (ref "R59") (pin "2") (pinfunction "2_2") (pintype "passive"))
      (node (ref "R61") (pin "2") (pinfunction "2_2") (pintype "passive"))
      (node (ref "R62") (pin "1") (pinfunction "1_1") (pintype "passive"))
      (node (ref "R65") (pin "1") (pinfunction "1_1") (pintype "passive"))
      (node (ref "R73") (pin "1") (pinfunction "1_1") (pintype "passive"))
      (node (ref "R83") (pin "2") (pinfunction "2_2") (pintype "passive"))
      (node (ref "SB1") (pin "2") (pinfunction "2_2") (pintype "passive"))
      (node (ref "SB1") (pin "Shield") (pinfunction "Shield_Shield") (pintype "passive"))
      (node (ref "VT1") (pin "S") (pinfunction "S_S") (pintype "passive"))
      (node (ref "VT2") (pin "S") (pinfunction "S_S") (pintype "passive"))
    )
    (net (code "55") (name "Net-(C122-Pad1)") (class "Default")
      (node (ref "C122") (pin "1") (pinfunction "1_1") (pintype "passive"))
      (node (ref "L1") (pin "2") (pinfunction "2_2") (pintype "passive"))
      (node (ref "R60") (pin "2") (pinfunction "2_2") (pintype "passive"))
    )
    (net (code "56") (name "Net-(C129-Pad1)") (class "Default")
      (node (ref "C129") (pin "1") (pinfunction "1_1") (pintype "passive"))
      (node (ref "J8") (pin "2") (pinfunction "2_2") (pintype "passive"))
      (node (ref "R69") (pin "2") (pinfunction "2_2") (pintype "passive"))
      (node (ref "R71") (pin "2") (pinfunction "2_2") (pintype "passive"))
    )
    (net (code "57") (name "Net-(C129-Pad2)") (class "Default")
      (node (ref "C129") (pin "2") (pinfunction "2_2") (pintype "passive"))
      (node (ref "J8") (pin "1") (pinfunction "1_1") (pintype "passive"))
      (node (ref "R73") (pin "2") (pinfunction "2_2") (pintype "passive"))
      (node (ref "VT1") (pin "D") (pinfunction "D_D") (pintype "passive"))
    )
    (net (code "58") (name "Net-(IC10-D_SEL)") (class "Default")
      (node (ref "IC10") (pin "2") (pinfunction "D_SEL_2") (pintype "passive"))
      (node (ref "R62") (pin "2") (pinfunction "2_2") (pintype "passive"))
    )
    (net (code "59") (name "Net-(IC10-RF_IN)") (class "Default")
      (node (ref "C120") (pin "2") (pinfunction "2_2") (pintype "passive"))
      (node (ref "IC10") (pin "11") (pinfunction "RF_IN_11") (pintype "passive"))
    )
    (net (code "60") (name "Net-(IC10-SAFEBOOT_N)") (class "Default")
      (node (ref "IC10") (pin "1") (pinfunction "SAFEBOOT_N_1") (pintype "passive"))
      (node (ref "R65") (pin "2") (pinfunction "2_2") (pintype "passive"))
    )
    (net (code "61") (name "Net-(IC10-V_BCKP)") (class "Default")
      (node (ref "C124") (pin "1") (pinfunction "1_1") (pintype "passive"))
      (node (ref "IC10") (pin "22") (pinfunction "V_BCKP_22") (pintype "passive"))
      (node (ref "R63") (pin "1") (pinfunction "1_1") (pintype "passive"))
      (node (ref "R64") (pin "1") (pinfunction "1_1") (pintype "passive"))
    )
    (net (code "62") (name "Net-(IC19-HOLD)") (class "Default")
      (node (ref "IC19") (pin "7") (pinfunction "HOLD_7") (pintype "passive"))
      (node (ref "R85") (pin "2") (pinfunction "2_2") (pintype "passive"))
    )
    (net (code "63") (name "Net-(IC19-W)") (class "Default")
      (node (ref "IC19") (pin "3") (pinfunction "W_3") (pintype "passive"))
      (node (ref "R86") (pin "2") (pinfunction "2_2") (pintype "passive"))
    )
    (net (code "64") (name "Net-(LED1-Pad3)") (class "Default")
      (node (ref "LED1") (pin "3") (pinfunction "3_3") (pintype "power_in"))
      (node (ref "R68") (pin "1") (pinfunction "1_1") (pintype "passive"))
    )
    (net (code "65") (name "Net-(LED1-Pad4)") (class "Default")
      (node (ref "LED1") (pin "4") (pinfunction "4_4") (pintype "power_in"))
      (node (ref "R70") (pin "1") (pinfunction "1_1") (pintype "passive"))
    )
    (net (code "66") (name "Net-(LED2-Pad3)") (class "Default")
      (node (ref "LED2") (pin "3") (pinfunction "3_3") (pintype "power_in"))
      (node (ref "R72") (pin "1") (pinfunction "1_1") (pintype "passive"))
    )
    (net (code "67") (name "Net-(LED2-Pad4)") (class "Default")
      (node (ref "LED2") (pin "4") (pinfunction "4_4") (pintype "power_in"))
      (node (ref "R74") (pin "1") (pinfunction "1_1") (pintype "passive"))
    )
    (net (code "68") (name "Net-(LED3-Pad3)") (class "Default")
      (node (ref "LED3") (pin "3") (pinfunction "3_3") (pintype "power_in"))
      (node (ref "R75") (pin "1") (pinfunction "1_1") (pintype "passive"))
    )
    (net (code "69") (name "Net-(LED3-Pad4)") (class "Default")
      (node (ref "LED3") (pin "4") (pinfunction "4_4") (pintype "power_in"))
      (node (ref "R76") (pin "1") (pinfunction "1_1") (pintype "passive"))
    )
    (net (code "70") (name "Net-(LED4-Pad3)") (class "Default")
      (node (ref "LED4") (pin "3") (pinfunction "3_3") (pintype "power_in"))
      (node (ref "R77") (pin "1") (pinfunction "1_1") (pintype "passive"))
    )
    (net (code "71") (name "Net-(LED4-Pad4)") (class "Default")
      (node (ref "LED4") (pin "4") (pinfunction "4_4") (pintype "power_in"))
      (node (ref "R78") (pin "1") (pinfunction "1_1") (pintype "passive"))
    )
    (net (code "72") (name "Net-(LED5-Pad3)") (class "Default")
      (node (ref "LED5") (pin "3") (pinfunction "3_3") (pintype "power_in"))
      (node (ref "R80") (pin "1") (pinfunction "1_1") (pintype "passive"))
    )
    (net (code "73") (name "Net-(LED5-Pad4)") (class "Default")
      (node (ref "LED5") (pin "4") (pinfunction "4_4") (pintype "power_in"))
      (node (ref "R82") (pin "1") (pinfunction "1_1") (pintype "passive"))
    )
    (net (code "74") (name "Net-(LED6-Pad1)") (class "Default")
      (node (ref "LED6") (pin "1") (pinfunction "1_1") (pintype "power_in"))
      (node (ref "R84") (pin "2") (pinfunction "2_2") (pintype "passive"))
    )
    (net (code "75") (name "Net-(LS1-Pad2)") (class "Default")
      (node (ref "LS1") (pin "2") (pinfunction "2_2") (pintype "passive"))
      (node (ref "R81") (pin "2") (pinfunction "2_2") (pintype "passive"))
      (node (ref "VT2") (pin "D") (pinfunction "D_D") (pintype "passive"))
    )
    (net (code "76") (name "Net-(R54-Pad1)") (class "Default")
      (node (ref "R54") (pin "1") (pinfunction "1_1") (pintype "passive"))
      (node (ref "R57") (pin "2") (pinfunction "2_2") (pintype "passive"))
      (node (ref "R60") (pin "1") (pinfunction "1_1") (pintype "passive"))
    )
    (net (code "77") (name "VCC1P8") (class "Default")
      (node (ref "R53") (pin "2") (pinfunction "2_2") (pintype "passive"))
      (node (ref "R79") (pin "1") (pinfunction "1_1") (pintype "passive"))
    )
    (net (code "78") (name "VCC3P0_BATT") (class "Default")
      (node (ref "J6") (pin "2") (pinfunction "2_2") (pintype "passive"))
      (node (ref "R63") (pin "2") (pinfunction "2_2") (pintype "passive"))
    )
    (net (code "79") (name "VCC3P3") (class "Default")
      (node (ref "C121") (pin "1") (pinfunction "1_1") (pintype "passive"))
      (node (ref "C123") (pin "2") (pinfunction "2_2") (pintype "passive"))
      (node (ref "C127") (pin "1") (pinfunction "1_1") (pintype "passive"))
      (node (ref "C128") (pin "2") (pinfunction "2_2") (pintype "passive"))
      (node (ref "C130") (pin "2") (pinfunction "2_2") (pintype "passive"))
      (node (ref "C131") (pin "1") (pinfunction "1_1") (pintype "passive"))
      (node (ref "C132") (pin "2") (pinfunction "2_2") (pintype "passive"))
      (node (ref "C134") (pin "1") (pinfunction "1_1") (pintype "passive"))
      (node (ref "IC11") (pin "10") (pinfunction "~{MR}_10") (pintype "input"))
      (node (ref "IC11") (pin "16") (pinfunction "VCC_16") (pintype "power_in"))
      (node (ref "IC12") (pin "8") (pinfunction "VCC_8") (pintype "power_in"))
      (node (ref "IC13") (pin "10") (pinfunction "~{MR}_10") (pintype "input"))
      (node (ref "IC13") (pin "16") (pinfunction "VCC_16") (pintype "power_in"))
      (node (ref "IC14") (pin "8") (pinfunction "VCC_8") (pintype "passive"))
      (node (ref "IC15") (pin "10") (pinfunction "~{MR}_10") (pintype "input"))
      (node (ref "IC15") (pin "16") (pinfunction "VCC_16") (pintype "power_in"))
      (node (ref "IC16") (pin "8") (pinfunction "VCC_8") (pintype "power_in"))
      (node (ref "IC17") (pin "8") (pinfunction "VCC_8") (pintype "power_in"))
      (node (ref "IC18") (pin "10") (pinfunction "~{MR}_10") (pintype "input"))
      (node (ref "IC18") (pin "16") (pinfunction "VCC_16") (pintype "power_in"))
      (node (ref "IC19") (pin "8") (pinfunction "VCC_8") (pintype "passive"))
      (node (ref "IC9") (pin "8") (pinfunction "VCC_8") (pintype "passive"))
      (node (ref "LED1") (pin "1") (pinfunction "1_1") (pintype "power_in"))
      (node (ref "LED1") (pin "2") (pinfunction "2_2") (pintype "power_in"))
      (node (ref "LED2") (pin "1") (pinfunction "1_1") (pintype "power_in"))
      (node (ref "LED2") (pin "2") (pinfunction "2_2") (pintype "power_in"))
      (node (ref "LED3") (pin "1") (pinfunction "1_1") (pintype "power_in"))
      (node (ref "LED3") (pin "2") (pinfunction "2_2") (pintype "power_in"))
      (node (ref "LED4") (pin "1") (pinfunction "1_1") (pintype "power_in"))
      (node (ref "LED4") (pin "2") (pinfunction "2_2") (pintype "power_in"))
      (node (ref "LED5") (pin "1") (pinfunction "1_1") (pintype "power_in"))
      (node (ref "LED5") (pin "2") (pinfunction "2_2") (pintype "power_in"))
      (node (ref "LS1") (pin "1") (pinfunction "1_1") (pintype "passive"))
      (node (ref "R55") (pin "1") (pinfunction "1_1") (pintype "passive"))
      (node (ref "R58") (pin "1") (pinfunction "1_1") (pintype "passive"))
      (node (ref "R69") (pin "1") (pinfunction "1_1") (pintype "passive"))
      (node (ref "R84") (pin "1") (pinfunction "1_1") (pintype "passive"))
      (node (ref "R85") (pin "1") (pinfunction "1_1") (pintype "passive"))
      (node (ref "R86") (pin "1") (pinfunction "1_1") (pintype "passive"))
    )
    (net (code "80") (name "VCC3P3_CLK") (class "Default")
      (node (ref "FR36") (pin "1") (pinfunction "1_1") (pintype "passive"))
    )
    (net (code "81") (name "VCC3P3_GNSS") (class "Default")
      (node (ref "C118") (pin "2") (pinfunction "2_2") (pintype "passive"))
      (node (ref "C119") (pin "2") (pinfunction "2_2") (pintype "passive"))
      (node (ref "C125") (pin "2") (pinfunction "2_2") (pintype "passive"))
      (node (ref "C126") (pin "1") (pinfunction "1_1") (pintype "passive"))
      (node (ref "FR36") (pin "2") (pinfunction "2_2") (pintype "passive"))
      (node (ref "IC10") (pin "23") (pinfunction "VCC_23") (pintype "passive"))
      (node (ref "R56") (pin "2") (pinfunction "2_2") (pintype "passive"))
      (node (ref "R57") (pin "1") (pinfunction "1_1") (pintype "passive"))
      (node (ref "R64") (pin "2") (pinfunction "2_2") (pintype "passive"))
    )
    (net (code "82") (name "VCC5P0") (class "Default")
      (node (ref "R71") (pin "1") (pinfunction "1_1") (pintype "passive"))
    )
    (net (code "83") (name "unconnected-(IC10-DDC_SCL{slash}SPI_CLK-Pad19)") (class "Default")
      (node (ref "IC10") (pin "19") (pinfunction "DDC_SCL/SPI_CLK_19") (pintype "passive+no_connect"))
    )
    (net (code "84") (name "unconnected-(IC10-DDC_SDA{slash}SPI_CSN-Pad18)") (class "Default")
      (node (ref "IC10") (pin "18") (pinfunction "DDC_SDA/SPI_CSN_18") (pintype "passive+no_connect"))
    )
    (net (code "85") (name "unconnected-(IC10-EXTINT-Pad4)") (class "Default")
      (node (ref "IC10") (pin "4") (pinfunction "EXTINT_4") (pintype "passive+no_connect"))
    )
    (net (code "86") (name "unconnected-(IC10-GEOFENCE_STAT{slash}RESV-Pad16)") (class "Default")
      (node (ref "IC10") (pin "16") (pinfunction "GEOFENCE_STAT/RESV_16") (pintype "passive+no_connect"))
    )
    (net (code "87") (name "unconnected-(IC10-LNA_EN{slash}RESV-Pad14)") (class "Default")
      (node (ref "IC10") (pin "14") (pinfunction "LNA_EN/RESV_14") (pintype "passive+no_connect"))
    )
    (net (code "88") (name "unconnected-(IC10-RESET_N-Pad8)") (class "Default")
      (node (ref "IC10") (pin "8") (pinfunction "RESET_N_8") (pintype "passive+no_connect"))
    )
    (net (code "89") (name "unconnected-(IC10-RESV-Pad17)") (class "Default")
      (node (ref "IC10") (pin "17") (pinfunction "RESV_17") (pintype "passive+no_connect"))
    )
    (net (code "90") (name "unconnected-(IC10-RTK_STAT{slash}RESV-Pad15)") (class "Default")
      (node (ref "IC10") (pin "15") (pinfunction "RTK_STAT/RESV_15") (pintype "passive+no_connect"))
    )
    (net (code "91") (name "unconnected-(IC15-Q7-Pad7)") (class "Default")
      (node (ref "IC15") (pin "7") (pinfunction "Q7_7") (pintype "output+no_connect"))
    )
    (net (code "92") (name "unconnected-(IC16-NC-Pad1)") (class "Default")
      (node (ref "IC16") (pin "1") (pinfunction "NC_1") (pintype "passive+no_connect"))
    )
    (net (code "93") (name "unconnected-(IC16-NC-Pad2)") (class "Default")
      (node (ref "IC16") (pin "2") (pinfunction "NC_2") (pintype "passive+no_connect"))
    )
    (net (code "94") (name "unconnected-(IC16-NC-Pad3)") (class "Default")
      (node (ref "IC16") (pin "3") (pinfunction "NC_3") (pintype "passive+no_connect"))
    )
    (net (code "95") (name "unconnected-(IC16-NC-Pad7)") (class "Default")
      (node (ref "IC16") (pin "7") (pinfunction "NC_7") (pintype "passive+no_connect"))
    )
    (net (code "96") (name "unconnected-(IC17-NC-Pad1)") (class "Default")
      (node (ref "IC17") (pin "1") (pinfunction "NC_1") (pintype "passive+no_connect"))
    )
    (net (code "97") (name "unconnected-(IC17-NC-Pad2)") (class "Default")
      (node (ref "IC17") (pin "2") (pinfunction "NC_2") (pintype "passive+no_connect"))
    )
    (net (code "98") (name "unconnected-(IC17-NC-Pad3)") (class "Default")
      (node (ref "IC17") (pin "3") (pinfunction "NC_3") (pintype "passive+no_connect"))
    )
    (net (code "99") (name "unconnected-(IC17-NC-Pad7)") (class "Default")
      (node (ref "IC17") (pin "7") (pinfunction "NC_7") (pintype "passive+no_connect"))
    )
    (net (code "100") (name "unconnected-(IC18-Q4-Pad4)") (class "Default")
      (node (ref "IC18") (pin "4") (pinfunction "Q4_4") (pintype "output+no_connect"))
    )
    (net (code "101") (name "unconnected-(IC18-Q5-Pad5)") (class "Default")
      (node (ref "IC18") (pin "5") (pinfunction "Q5_5") (pintype "output+no_connect"))
    )
    (net (code "102") (name "unconnected-(IC18-Q6-Pad6)") (class "Default")
      (node (ref "IC18") (pin "6") (pinfunction "Q6_6") (pintype "output+no_connect"))
    )
    (net (code "103") (name "unconnected-(IC18-Q7-Pad7)") (class "Default")
      (node (ref "IC18") (pin "7") (pinfunction "Q7_7") (pintype "output+no_connect"))
    )
    (net (code "104") (name "unconnected-(LED6-Pad2)") (class "Default")
      (node (ref "LED6") (pin "2") (pinfunction "2_2") (pintype "power_in+no_connect"))
    )
    (net (code "105") (name "unconnected-(LED6-Pad4)") (class "Default")
      (node (ref "LED6") (pin "4") (pinfunction "4_4") (pintype "power_in+no_connect"))
    )
  )
)
